# CURRENT_MONITOR.net
KiCad netlist of a schematic drawn in Altium Designer
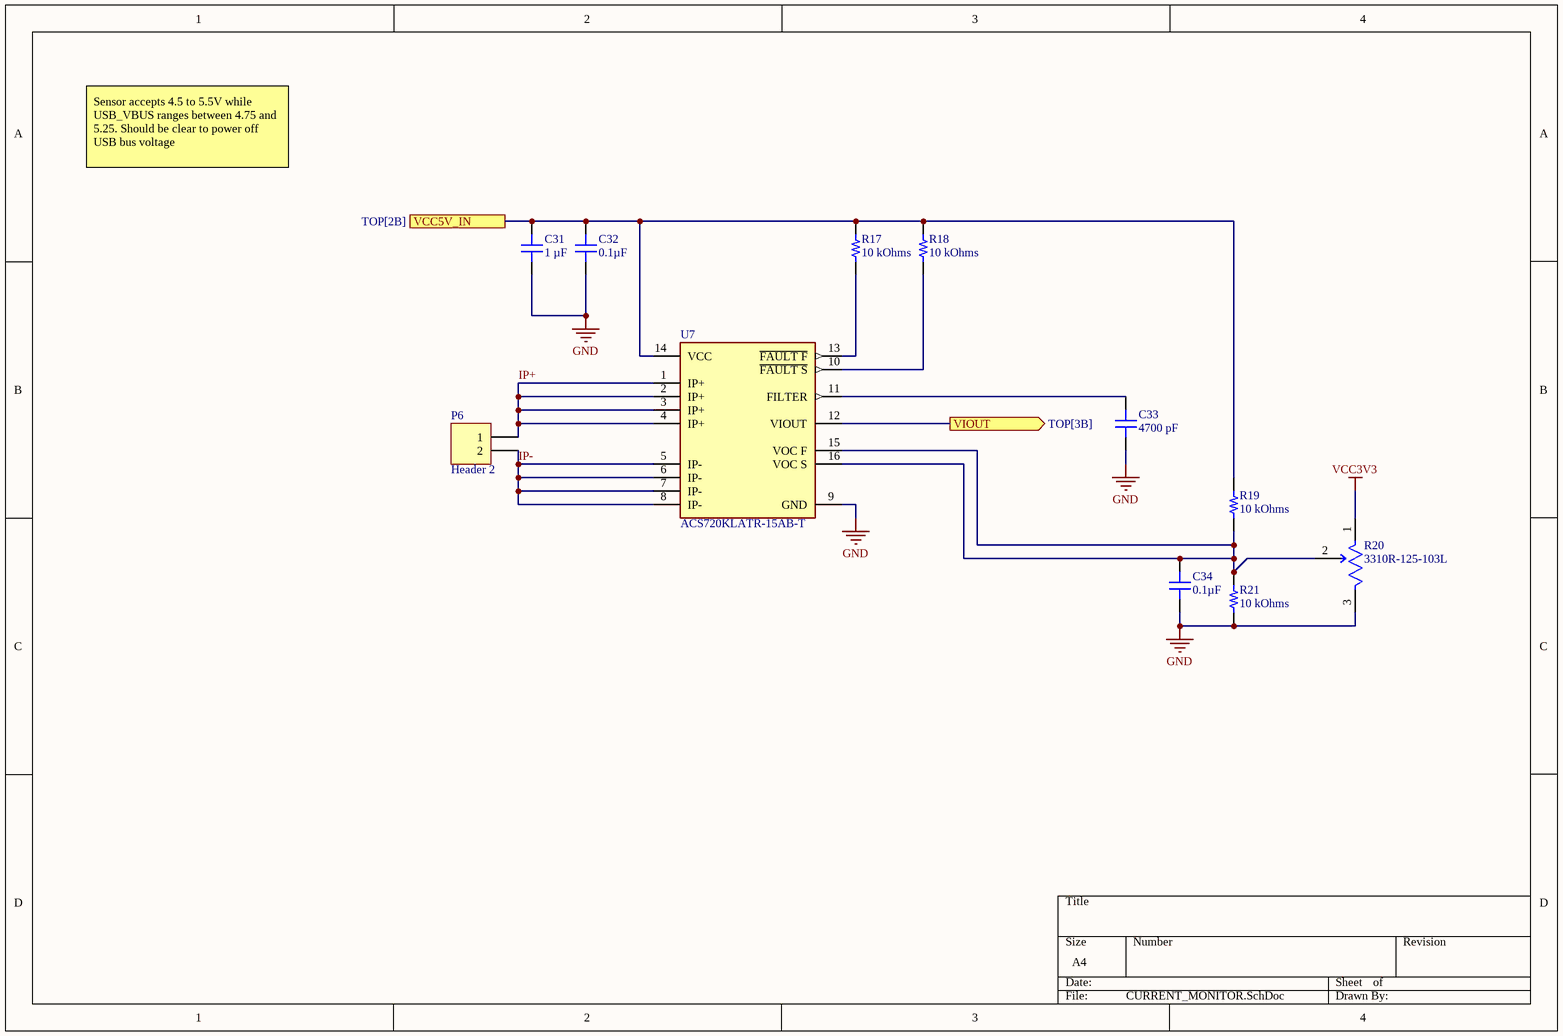
[diagram p0: CURRENT_MONITOR.SchDoc]

(export (version "E")
  (design (tool "Eeschema 10.0.6"))
  (components
    (comp (ref "C31")
      (value "1 µF")
      (footprint "CAP 0603_1608")
      (description "CAP CER 1UF 16V X7R 0603")
      (fields (field (name "PART NUMBER") "C0603C105K4RACAUTO") (field (name "MANUFACTURER") "KEMET"))
      (libsource (lib "Celestial") (part "Capacitor"))
    )
    (comp (ref "C32")
      (value "0.1µF")
      (footprint "CAP 0402_1005")
      (description "CAP CER 0.1UF 10V X7R 0402")
      (fields (field (name "PART NUMBER") "0402ZC104KAT2A") (field (name "MANUFACTURER") "AVX Corporation"))
      (libsource (lib "Celestial") (part "Capacitor"))
    )
    (comp (ref "C33")
      (value "4700 pF")
      (footprint "CAP 0603_1608")
      (description "CAP CER 0603 4.7NF 16V X7R 10%")
      (fields (field (name "PART NUMBER") "C0603C472K4RECAUTO") (field (name "MANUFACTURER") "KEMET"))
      (libsource (lib "Celestial") (part "Capacitor"))
    )
    (comp (ref "C34")
      (value "0.1µF")
      (footprint "CAP 0402_1005")
      (description "CAP CER 0.1UF 10V X7R 0402")
      (fields (field (name "PART NUMBER") "0402ZC104KAT2A") (field (name "MANUFACTURER") "AVX Corporation"))
      (libsource (lib "Celestial") (part "Capacitor"))
    )
    (comp (ref "P6")
      (value "Header 2")
      (footprint "HDR1X2")
      (description "Header, 2-Pin")
      (fields (field (name "PUBLISHER") "Altium Limited"))
      (libsource (lib "Miscellaneous Connectors") (part "Header 2"))
    )
    (comp (ref "R17")
      (value "10 kOhms")
      (footprint "RES 0402_1005")
      (description "RES 10K OHM 0.1% 1/10W 0402")
      (fields
        (field (name "PART NUMBER") "RP73PF1E10KBTD")
        (field (name "MANUFACTURER") "TE Connectivity Passive Product")
      )
      (libsource (lib "Celestial") (part "Resistor"))
    )
    (comp (ref "R18")
      (value "10 kOhms")
      (footprint "RES 0402_1005")
      (description "RES 10K OHM 0.1% 1/10W 0402")
      (fields
        (field (name "PART NUMBER") "RP73PF1E10KBTD")
        (field (name "MANUFACTURER") "TE Connectivity Passive Product")
      )
      (libsource (lib "Celestial") (part "Resistor"))
    )
    (comp (ref "R19")
      (value "10 kOhms")
      (footprint "RES 0402_1005")
      (description "RES 10K OHM 0.1% 1/10W 0402")
      (fields
        (field (name "PART NUMBER") "RP73PF1E10KBTD")
        (field (name "MANUFACTURER") "TE Connectivity Passive Product")
      )
      (libsource (lib "Celestial") (part "Resistor"))
    )
    (comp (ref "R20")
      (value "3310R-125-103L")
      (footprint "FP-3310R-MFG")
      (description "POT 10K OHM 1/4W PLASTIC LINEAR")
      (fields (field (name "TOLERANCE") "20%"))
      (libsource (lib "Altium Content Vault") (part "cfaf082cc24db979c98760cc608bf4a"))
    )
    (comp (ref "R21")
      (value "10 kOhms")
      (footprint "RES 0402_1005")
      (description "RES 10K OHM 0.1% 1/10W 0402")
      (fields
        (field (name "PART NUMBER") "RP73PF1E10KBTD")
        (field (name "MANUFACTURER") "TE Connectivity Passive Product")
      )
      (libsource (lib "Celestial") (part "Resistor"))
    )
    (comp (ref "U7")
      (value "ACS720KLATR-15AB-T")
      (footprint "FP-LA-16-IPC_A")
      (description "CURRENT SENSOR")
      (libsource (lib "Altium Content Vault") (part "e7c41c7680a8add6b5da1b4c61faca3"))
    )
  )
  (nets
    (net (code "1") (name "/IP+") (class "Default")
      (node (ref "P6") (pin "1") (pinfunction "1_1") (pintype "passive"))
      (node (ref "U7") (pin "1") (pinfunction "IP+_1") (pintype "passive"))
      (node (ref "U7") (pin "2") (pinfunction "IP+_2") (pintype "passive"))
      (node (ref "U7") (pin "3") (pinfunction "IP+_3") (pintype "passive"))
      (node (ref "U7") (pin "4") (pinfunction "IP+_4") (pintype "passive"))
    )
    (net (code "2") (name "/IP-") (class "Default")
      (node (ref "P6") (pin "2") (pinfunction "2_2") (pintype "passive"))
      (node (ref "U7") (pin "5") (pinfunction "IP-_5") (pintype "passive"))
      (node (ref "U7") (pin "6") (pinfunction "IP-_6") (pintype "passive"))
      (node (ref "U7") (pin "7") (pinfunction "IP-_7") (pintype "passive"))
      (node (ref "U7") (pin "8") (pinfunction "IP-_8") (pintype "passive"))
    )
    (net (code "3") (name "/VCC5V_IN") (class "Default")
      (node (ref "C31") (pin "2") (pinfunction "2_2") (pintype "passive"))
      (node (ref "C32") (pin "2") (pinfunction "2_2") (pintype "passive"))
      (node (ref "R17") (pin "2") (pinfunction "2_2") (pintype "passive"))
      (node (ref "R18") (pin "2") (pinfunction "2_2") (pintype "passive"))
      (node (ref "R19") (pin "2") (pinfunction "2_2") (pintype "passive"))
      (node (ref "U7") (pin "14") (pinfunction "VCC_14") (pintype "power_in"))
    )
    (net (code "4") (name "/VIOUT") (class "Default")
      (node (ref "U7") (pin "12") (pinfunction "VIOUT_12") (pintype "passive"))
    )
    (net (code "5") (name "GND") (class "Default")
      (node (ref "C31") (pin "1") (pinfunction "1_1") (pintype "passive"))
      (node (ref "C32") (pin "1") (pinfunction "1_1") (pintype "passive"))
      (node (ref "C33") (pin "1") (pinfunction "1_1") (pintype "passive"))
      (node (ref "C34") (pin "1") (pinfunction "1_1") (pintype "passive"))
      (node (ref "R20") (pin "3") (pinfunction "CW_3") (pintype "passive"))
      (node (ref "R21") (pin "1") (pinfunction "1_1") (pintype "passive"))
      (node (ref "U7") (pin "9") (pinfunction "GND_9") (pintype "power_in"))
    )
    (net (code "6") (name "Net-(U7-FILTER)") (class "Default")
      (node (ref "C33") (pin "2") (pinfunction "2_2") (pintype "passive"))
      (node (ref "U7") (pin "11") (pinfunction "FILTER_11") (pintype "output"))
    )
    (net (code "7") (name "Net-(U7-VOC_F)") (class "Default")
      (node (ref "C34") (pin "2") (pinfunction "2_2") (pintype "passive"))
      (node (ref "R19") (pin "1") (pinfunction "1_1") (pintype "passive"))
      (node (ref "R20") (pin "2") (pinfunction "2_2") (pintype "passive"))
      (node (ref "R21") (pin "2") (pinfunction "2_2") (pintype "passive"))
      (node (ref "U7") (pin "15") (pinfunction "VOC_F_15") (pintype "power_in"))
      (node (ref "U7") (pin "16") (pinfunction "VOC_S_16") (pintype "power_in"))
    )
    (net (code "8") (name "Net-(U7-~{FAULT_F})") (class "Default")
      (node (ref "R17") (pin "1") (pinfunction "1_1") (pintype "passive"))
      (node (ref "U7") (pin "13") (pinfunction "~{FAULT_F}_13") (pintype "output"))
    )
    (net (code "9") (name "Net-(U7-~{FAULT_S})") (class "Default")
      (node (ref "R18") (pin "1") (pinfunction "1_1") (pintype "passive"))
      (node (ref "U7") (pin "10") (pinfunction "~{FAULT_S}_10") (pintype "output"))
    )
    (net (code "10") (name "VCC3V3") (class "Default")
      (node (ref "R20") (pin "1") (pinfunction "CCW_1") (pintype "passive"))
    )
  )
)
